# controller_8266.net
KiCad netlist of a schematic drawn in Altium Designer
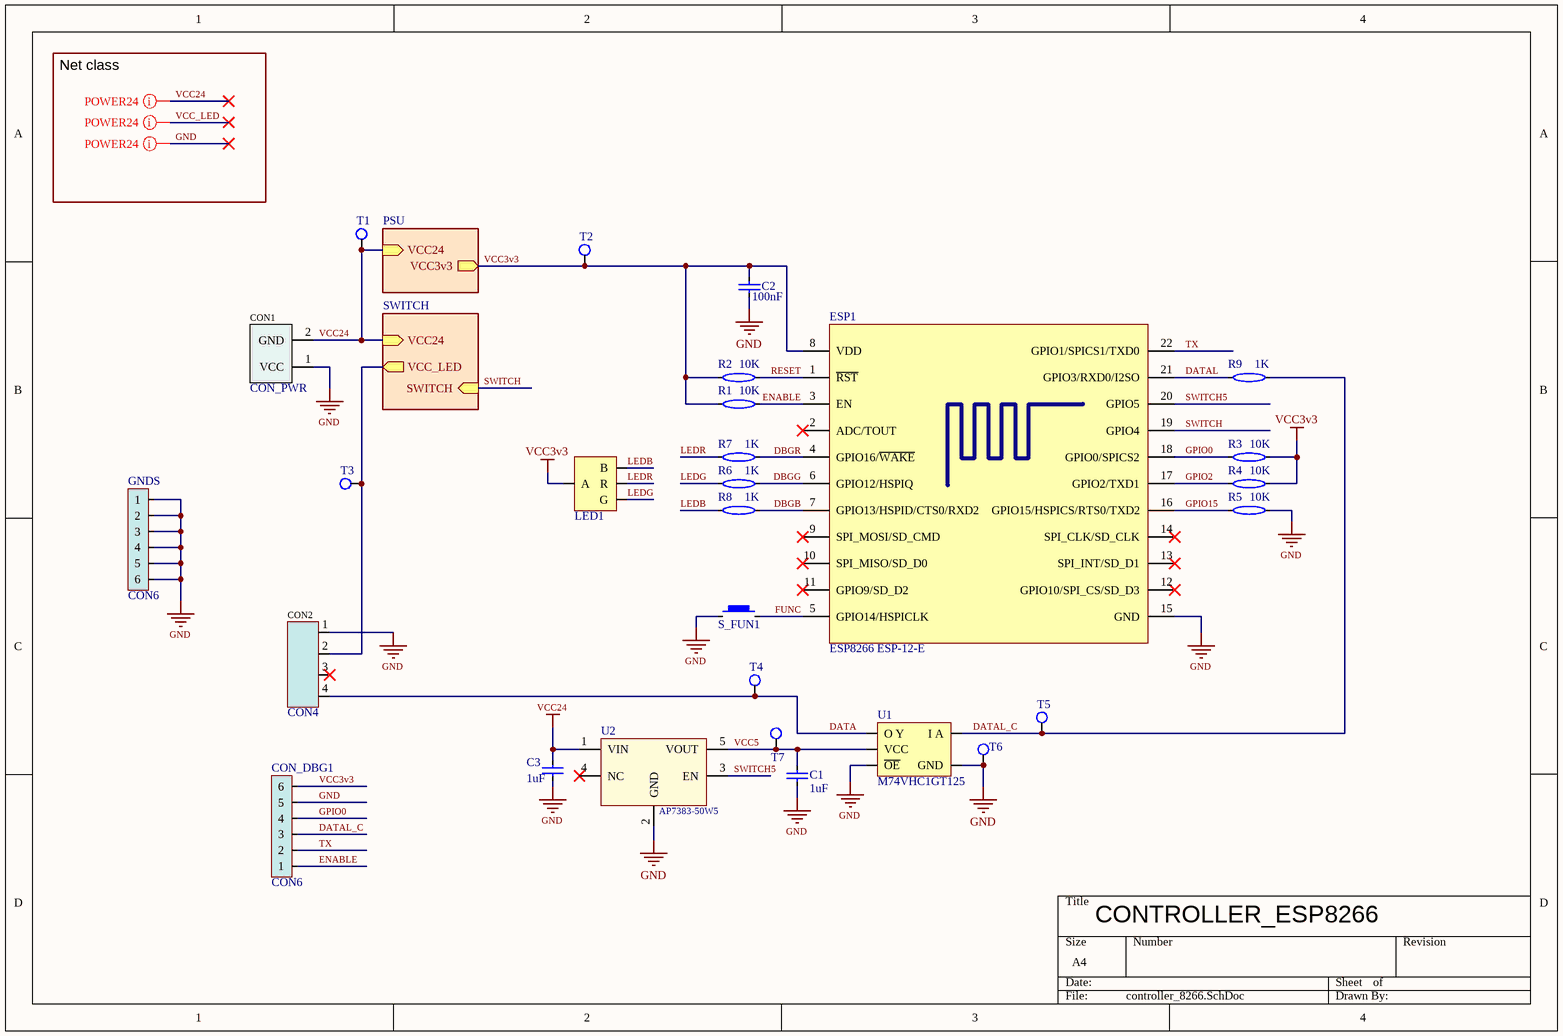
[diagram p0: controller_8266.SchDoc]

(export (version "E")
  (design (tool "Eeschema 10.0.6"))
  (components
    (comp (ref "C1")
      (value "1uF")
      (footprint "CAPC_0603_1608X08L")
      (description "Capacitor")
      (fields (field (name "Comment") "Cap") (field (name "PUBLISHER") "Altium Limited"))
      (libsource (lib "controller_8266") (part "Cap"))
    )
    (comp (ref "C2")
      (value "100nF")
      (footprint "CAPC_0603_1608X08L")
      (description "Capacitor")
      (fields (field (name "Comment") "Cap") (field (name "PUBLISHER") "Altium Limited"))
      (libsource (lib "controller_8266") (part "Cap"))
    )
    (comp (ref "C3")
      (value "1uF")
      (footprint "CAPC_0603_1608X08L")
      (description "Capacitor")
      (fields (field (name "Comment") "Cap") (field (name "PUBLISHER") "Altium Limited"))
      (libsource (lib "controller_8266") (part "Cap"))
    )
    (comp (ref "CON1")
      (value "CON_PWR")
      (footprint "CONPWR")
      (description "Header 2 way")
      (libsource (lib "controller_8266") (part "CON_PWR"))
    )
    (comp (ref "CON2")
      (value "CON4")
      (footprint "CONNECTOR")
      (description "Header 4 way")
      (libsource (lib "controller_8266") (part "CON4"))
    )
    (comp (ref "CON_DBG1")
      (value "CON6")
      (footprint "CON2X3")
      (description "Debug header 6 way")
      (libsource (lib "") (part "CON6_1"))
    )
    (comp (ref "ESP1")
      (value "ESP8266 ESP-12-E")
      (footprint "ESP8266 ESP-12-E")
      (libsource (lib "controller_8266") (part "ESP8266 ESP-12-E"))
    )
    (comp (ref "GNDS")
      (value "CON6")
      (footprint "CON2X3")
      (description "Debug header 6 way")
      (libsource (lib "controller_8266") (part "CON6"))
    )
    (comp (ref "LED1")
      (value "RGB LED Common anode")
      (footprint "PLCC-4")
      (description "Dot is _not_ anode!")
      (libsource (lib "controller_8266") (part "RGB_LED"))
    )
    (comp (ref "R1")
      (value "10K")
      (footprint "RESC_0603_1608X08L")
      (description "Resistor")
      (fields (field (name "Comment") "Res2") (field (name "PUBLISHER") "Altium Limited"))
      (libsource (lib "controller_8266") (part "Res2"))
    )
    (comp (ref "R2")
      (value "10K")
      (footprint "RESC_0603_1608X08L")
      (description "Resistor")
      (fields (field (name "Comment") "Res2") (field (name "PUBLISHER") "Altium Limited"))
      (libsource (lib "controller_8266") (part "Res2"))
    )
    (comp (ref "R3")
      (value "10K")
      (footprint "RESC_0603_1608X08L")
      (description "Resistor")
      (fields (field (name "Comment") "Res2") (field (name "PUBLISHER") "Altium Limited"))
      (libsource (lib "controller_8266") (part "Res2"))
    )
    (comp (ref "R4")
      (value "10K")
      (footprint "RESC_0603_1608X08L")
      (description "Resistor")
      (fields (field (name "Comment") "Res2") (field (name "PUBLISHER") "Altium Limited"))
      (libsource (lib "controller_8266") (part "Res2"))
    )
    (comp (ref "R5")
      (value "10K")
      (footprint "RESC_0603_1608X08L")
      (description "Resistor")
      (fields (field (name "Comment") "Res2") (field (name "PUBLISHER") "Altium Limited"))
      (libsource (lib "controller_8266") (part "Res2"))
    )
    (comp (ref "R6")
      (value "1K")
      (footprint "RESC_0603_1608X08L")
      (description "Resistor")
      (fields (field (name "Comment") "Res2") (field (name "PUBLISHER") "Altium Limited"))
      (libsource (lib "controller_8266") (part "Res2"))
    )
    (comp (ref "R7")
      (value "1K")
      (footprint "RESC_0603_1608X08L")
      (description "Resistor")
      (fields (field (name "Comment") "Res2") (field (name "PUBLISHER") "Altium Limited"))
      (libsource (lib "controller_8266") (part "Res2"))
    )
    (comp (ref "R8")
      (value "1K")
      (footprint "RESC_0603_1608X08L")
      (description "Resistor")
      (fields (field (name "Comment") "Res2") (field (name "PUBLISHER") "Altium Limited"))
      (libsource (lib "controller_8266") (part "Res2"))
    )
    (comp (ref "R9")
      (value "1K")
      (footprint "RESC_0603_1608X08L")
      (description "Resistor")
      (fields (field (name "Comment") "Res2") (field (name "PUBLISHER") "Altium Limited"))
      (libsource (lib "controller_8266") (part "Res2"))
    )
    (comp (ref "S_FUN1")
      (value "4-1437565-1")
      (footprint "EVQP7C01P")
      (description "Tactile switch")
      (fields (field (name "RS PART NUMBER") "1616046"))
      (libsource (lib "controller_8266") (part "4-1437565-1"))
    )
    (comp (ref "T1")
      (value "Testpoint")
      (footprint "TESTPOINT")
      (libsource (lib "controller_8266") (part "Testpoint"))
    )
    (comp (ref "T2")
      (value "Testpoint")
      (footprint "TESTPOINT")
      (libsource (lib "controller_8266") (part "Testpoint"))
    )
    (comp (ref "T3")
      (value "Testpoint")
      (footprint "TESTPOINT")
      (libsource (lib "controller_8266") (part "Testpoint"))
    )
    (comp (ref "T4")
      (value "Testpoint")
      (footprint "TESTPOINT")
      (libsource (lib "controller_8266") (part "Testpoint"))
    )
    (comp (ref "T5")
      (value "Testpoint")
      (footprint "TESTPOINT")
      (libsource (lib "controller_8266") (part "Testpoint"))
    )
    (comp (ref "T6")
      (value "Testpoint")
      (footprint "TESTPOINT")
      (libsource (lib "controller_8266") (part "Testpoint"))
    )
    (comp (ref "T7")
      (value "Testpoint")
      (footprint "TESTPOINT")
      (libsource (lib "controller_8266") (part "Testpoint"))
    )
    (comp (ref "U1")
      (value "M74VHC1GT125")
      (footprint "SOT95P285X130-5N")
      (description "Level shifter non inverting")
      (libsource (lib "controller_8266") (part "M74VHC1GT125"))
    )
    (comp (ref "U2")
      (value "AP7383-50W5")
      (footprint "SOT95P285X130-5N")
      (libsource (lib "controller_8266") (part "AP7383-50W5"))
    )
  )
  (nets
    (net (code "1") (name "/DATA") (class "Default")
      (node (ref "CON2") (pin "4") (pintype "passive"))
      (node (ref "T4") (pin "1") (pinfunction "VOUT_1") (pintype "passive"))
      (node (ref "U1") (pin "4") (pinfunction "O_Y_4") (pintype "passive"))
    )
    (net (code "2") (name "/DATAL") (class "Default")
      (node (ref "ESP1") (pin "21") (pinfunction "GPIO3/RXD0/I2SO_21") (pintype "passive"))
      (node (ref "R9") (pin "2") (pinfunction "2_2") (pintype "passive"))
    )
    (net (code "3") (name "/DATAL_C") (class "Default")
      (node (ref "CON_DBG1") (pin "3") (pinfunction "3_3") (pintype "passive"))
      (node (ref "R9") (pin "1") (pinfunction "1_1") (pintype "passive"))
      (node (ref "T5") (pin "1") (pinfunction "VOUT_1") (pintype "passive"))
      (node (ref "U1") (pin "2") (pinfunction "I_A_2") (pintype "passive"))
    )
    (net (code "4") (name "/DBGB") (class "Default")
      (node (ref "ESP1") (pin "7") (pinfunction "GPIO13/HSPID/CTS0/RXD2_7") (pintype "passive"))
      (node (ref "R8") (pin "2") (pinfunction "2_2") (pintype "passive"))
    )
    (net (code "5") (name "/DBGG") (class "Default")
      (node (ref "ESP1") (pin "6") (pinfunction "GPIO12/HSPIQ_6") (pintype "passive"))
      (node (ref "R6") (pin "2") (pinfunction "2_2") (pintype "passive"))
    )
    (net (code "7") (name "/DBGR") (class "Default")
      (node (ref "ESP1") (pin "4") (pinfunction "GPIO16/~{WAKE}_4") (pintype "passive"))
      (node (ref "R7") (pin "2") (pinfunction "2_2") (pintype "passive"))
    )
    (net (code "8") (name "/ENABLE") (class "Default")
      (node (ref "CON_DBG1") (pin "1") (pinfunction "1_1") (pintype "passive"))
      (node (ref "ESP1") (pin "3") (pinfunction "EN_3") (pintype "passive"))
      (node (ref "R1") (pin "2") (pinfunction "2_2") (pintype "passive"))
    )
    (net (code "9") (name "/FUNC") (class "Default")
      (node (ref "ESP1") (pin "5") (pinfunction "GPIO14/HSPICLK_5") (pintype "passive"))
      (node (ref "S_FUN1") (pin "1") (pinfunction "1_1") (pintype "passive"))
    )
    (net (code "10") (name "/GPIO0") (class "Default")
      (node (ref "CON_DBG1") (pin "4") (pinfunction "4_4") (pintype "passive"))
      (node (ref "ESP1") (pin "18") (pinfunction "GPIO0/SPICS2_18") (pintype "passive"))
      (node (ref "R3") (pin "1") (pinfunction "1_1") (pintype "passive"))
    )
    (net (code "11") (name "/GPIO2") (class "Default")
      (node (ref "ESP1") (pin "17") (pinfunction "GPIO2/TXD1_17") (pintype "passive"))
      (node (ref "R4") (pin "1") (pinfunction "1_1") (pintype "passive"))
    )
    (net (code "12") (name "/GPIO15") (class "Default")
      (node (ref "ESP1") (pin "16") (pinfunction "GPIO15/HSPICS/RTS0/TXD2_16") (pintype "passive"))
      (node (ref "R5") (pin "1") (pinfunction "1_1") (pintype "passive"))
    )
    (net (code "13") (name "/LEDB") (class "Default")
      (node (ref "LED1") (pin "B") (pinfunction "B_B") (pintype "passive"))
      (node (ref "R8") (pin "1") (pinfunction "1_1") (pintype "passive"))
    )
    (net (code "14") (name "/LEDG") (class "Default")
      (node (ref "LED1") (pin "G") (pinfunction "G_G") (pintype "passive"))
      (node (ref "R6") (pin "1") (pinfunction "1_1") (pintype "passive"))
    )
    (net (code "15") (name "/LEDR") (class "Default")
      (node (ref "LED1") (pin "R") (pinfunction "R_R") (pintype "passive"))
      (node (ref "R7") (pin "1") (pinfunction "1_1") (pintype "passive"))
    )
    (net (code "16") (name "/RESET") (class "Default")
      (node (ref "ESP1") (pin "1") (pinfunction "~{RST}_1") (pintype "passive"))
      (node (ref "R2") (pin "1") (pinfunction "1_1") (pintype "passive"))
    )
    (net (code "17") (name "/SWITCH") (class "Default")
      (node (ref "ESP1") (pin "19") (pinfunction "GPIO4_19") (pintype "passive"))
    )
    (net (code "18") (name "/SWITCH5") (class "Default")
      (node (ref "ESP1") (pin "20") (pinfunction "GPIO5_20") (pintype "passive"))
      (node (ref "U2") (pin "3") (pinfunction "EN_3") (pintype "passive"))
    )
    (net (code "19") (name "/TX") (class "Default")
      (node (ref "CON_DBG1") (pin "2") (pinfunction "2_2") (pintype "passive"))
      (node (ref "ESP1") (pin "22") (pinfunction "GPIO1/SPICS1/TXD0_22") (pintype "passive"))
    )
    (net (code "21") (name "/VCC5") (class "Default")
      (node (ref "C1") (pin "2") (pinfunction "2_2") (pintype "passive"))
      (node (ref "T7") (pin "1") (pinfunction "VOUT_1") (pintype "passive"))
      (node (ref "U1") (pin "5") (pinfunction "VCC_5") (pintype "passive"))
      (node (ref "U2") (pin "5") (pinfunction "VOUT_5") (pintype "passive"))
    )
    (net (code "22") (name "/VCC_LED_1") (class "Default")
      (node (ref "CON2") (pin "2") (pintype "passive"))
      (node (ref "T3") (pin "1") (pinfunction "VOUT_1") (pintype "passive"))
    )
    (net (code "23") (name "GND") (class "Default")
      (node (ref "C1") (pin "1") (pinfunction "1_1") (pintype "passive"))
      (node (ref "C2") (pin "2") (pinfunction "2_2") (pintype "passive"))
      (node (ref "C3") (pin "1") (pinfunction "1_1") (pintype "passive"))
      (node (ref "CON1") (pin "1") (pinfunction "VCC_1") (pintype "passive"))
      (node (ref "CON2") (pin "1") (pintype "passive"))
      (node (ref "CON_DBG1") (pin "5") (pinfunction "5_5") (pintype "passive"))
      (node (ref "ESP1") (pin "15") (pinfunction "GND_15") (pintype "passive"))
      (node (ref "GNDS") (pin "1") (pinfunction "1_1") (pintype "passive"))
      (node (ref "GNDS") (pin "2") (pinfunction "2_2") (pintype "passive"))
      (node (ref "GNDS") (pin "3") (pinfunction "3_3") (pintype "passive"))
      (node (ref "GNDS") (pin "4") (pinfunction "4_4") (pintype "passive"))
      (node (ref "GNDS") (pin "5") (pinfunction "5_5") (pintype "passive"))
      (node (ref "GNDS") (pin "6") (pinfunction "6_6") (pintype "passive"))
      (node (ref "R5") (pin "2") (pinfunction "2_2") (pintype "passive"))
      (node (ref "S_FUN1") (pin "2") (pinfunction "2_2") (pintype "passive"))
      (node (ref "T6") (pin "1") (pinfunction "VOUT_1") (pintype "passive"))
      (node (ref "U1") (pin "1") (pinfunction "~{OE}_1") (pintype "passive"))
      (node (ref "U1") (pin "3") (pinfunction "GND_3") (pintype "passive"))
      (node (ref "U2") (pin "2") (pinfunction "GND_2") (pintype "passive"))
    )
    (net (code "24") (name "VCC3v3") (class "Default")
      (node (ref "C2") (pin "1") (pinfunction "1_1") (pintype "passive"))
      (node (ref "CON_DBG1") (pin "6") (pinfunction "6_6") (pintype "passive"))
      (node (ref "ESP1") (pin "8") (pinfunction "VDD_8") (pintype "passive"))
      (node (ref "LED1") (pin "A") (pinfunction "A_A") (pintype "passive"))
      (node (ref "R1") (pin "1") (pinfunction "1_1") (pintype "passive"))
      (node (ref "R2") (pin "2") (pinfunction "2_2") (pintype "passive"))
      (node (ref "R3") (pin "2") (pinfunction "2_2") (pintype "passive"))
      (node (ref "R4") (pin "2") (pinfunction "2_2") (pintype "passive"))
      (node (ref "T2") (pin "1") (pinfunction "VOUT_1") (pintype "passive"))
    )
    (net (code "25") (name "VCC24") (class "Default")
      (node (ref "C3") (pin "2") (pinfunction "2_2") (pintype "passive"))
      (node (ref "CON1") (pin "2") (pinfunction "GND_2") (pintype "passive"))
      (node (ref "T1") (pin "1") (pinfunction "VOUT_1") (pintype "passive"))
      (node (ref "U2") (pin "1") (pinfunction "VIN_1") (pintype "passive"))
    )
    (net (code "26") (name "unconnected-(CON2-Pad3)") (class "Default")
      (node (ref "CON2") (pin "3") (pintype "passive+no_connect"))
    )
    (net (code "27") (name "unconnected-(ESP1-ADC{slash}TOUT-Pad2)") (class "Default")
      (node (ref "ESP1") (pin "2") (pinfunction "ADC/TOUT_2") (pintype "passive+no_connect"))
    )
    (net (code "28") (name "unconnected-(ESP1-GPIO9{slash}SD_D2-Pad11)") (class "Default")
      (node (ref "ESP1") (pin "11") (pinfunction "GPIO9/SD_D2_11") (pintype "passive+no_connect"))
    )
    (net (code "29") (name "unconnected-(ESP1-GPIO10{slash}SPI_CS{slash}SD_D3-Pad12)") (class "Default")
      (node (ref "ESP1") (pin "12") (pinfunction "GPIO10/SPI_CS/SD_D3_12") (pintype "passive+no_connect"))
    )
    (net (code "30") (name "unconnected-(ESP1-SPI_CLK{slash}SD_CLK-Pad14)") (class "Default")
      (node (ref "ESP1") (pin "14") (pinfunction "SPI_CLK/SD_CLK_14") (pintype "passive+no_connect"))
    )
    (net (code "31") (name "unconnected-(ESP1-SPI_INT{slash}SD_D1-Pad13)") (class "Default")
      (node (ref "ESP1") (pin "13") (pinfunction "SPI_INT/SD_D1_13") (pintype "passive+no_connect"))
    )
    (net (code "32") (name "unconnected-(ESP1-SPI_MISO{slash}SD_D0-Pad10)") (class "Default")
      (node (ref "ESP1") (pin "10") (pinfunction "SPI_MISO/SD_D0_10") (pintype "passive+no_connect"))
    )
    (net (code "33") (name "unconnected-(ESP1-SPI_MOSI{slash}SD_CMD-Pad9)") (class "Default")
      (node (ref "ESP1") (pin "9") (pinfunction "SPI_MOSI/SD_CMD_9") (pintype "passive+no_connect"))
    )
    (net (code "34") (name "unconnected-(U2-NC-Pad4)") (class "Default")
      (node (ref "U2") (pin "4") (pinfunction "NC_4") (pintype "passive+no_connect"))
    )
  )
)
